# MODULO_CONTROL.net
KiCad netlist of a schematic drawn in Altium Designer
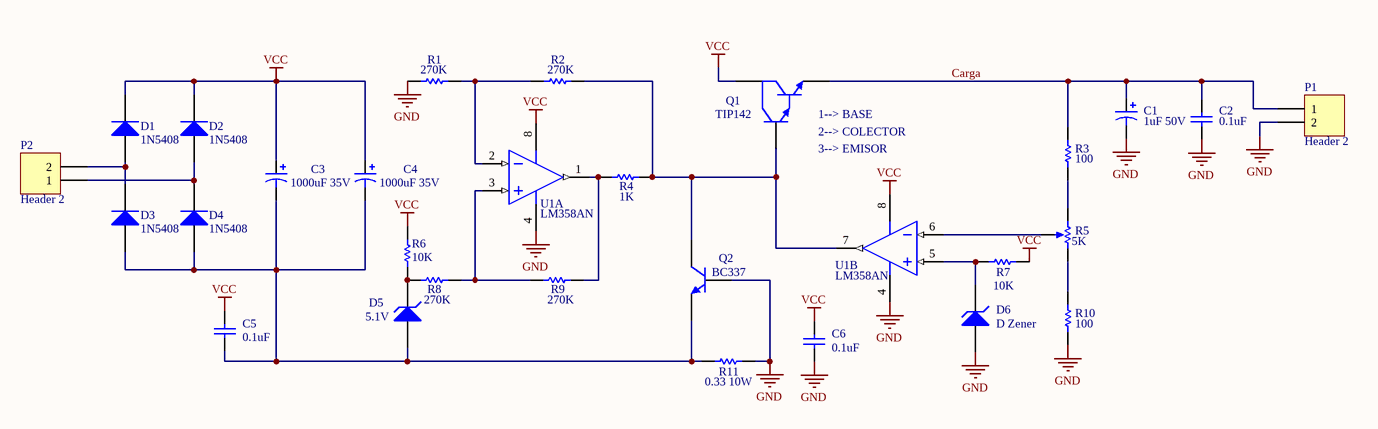
[diagram p0: MODULO CONTROL.SchDoc]

(export (version "E")
  (design (tool "Eeschema 10.0.6"))
  (components
    (comp (ref "C1")
      (value "1uF 50V")
      (footprint "CAPPR2-5x6.8")
      (description "Polarized Capacitor (Radial)")
      (fields (field (name "Comment") "Cap Pol1") (field (name "PUBLISHER") "Altium Limited"))
      (libsource (lib "Miscellaneous Devices") (part "Cap Pol1"))
    )
    (comp (ref "C2")
      (value "0.1uF")
      (footprint "Miscellaneous Devices:RAD-0.2")
      (description "Capacitor")
      (fields (field (name "Comment") "Cap") (field (name "PUBLISHER") "Altium Limited"))
      (libsource (lib "Miscellaneous Devices") (part "Cap"))
    )
    (comp (ref "C3")
      (value "1000uF 35V")
      (footprint "RB5-10.5")
      (description "Polarized Capacitor (Radial)")
      (fields (field (name "Comment") "Cap Pol1") (field (name "PUBLISHER") "Altium Limited"))
      (libsource (lib "Miscellaneous Devices") (part "Cap Pol1"))
    )
    (comp (ref "C4")
      (value "1000uF 35V")
      (footprint "RB5-10.5")
      (description "Polarized Capacitor (Radial)")
      (fields (field (name "Comment") "Cap Pol1") (field (name "PUBLISHER") "Altium Limited"))
      (libsource (lib "Miscellaneous Devices") (part "Cap Pol1"))
    )
    (comp (ref "C5")
      (value "0.1uF")
      (footprint "Miscellaneous Devices:RAD-0.2")
      (description "Capacitor")
      (fields (field (name "Comment") "Cap") (field (name "PUBLISHER") "Altium Limited"))
      (libsource (lib "Miscellaneous Devices") (part "Cap"))
    )
    (comp (ref "C6")
      (value "0.1uF")
      (footprint "RAD-0.2")
      (description "Capacitor")
      (fields (field (name "Comment") "Cap") (field (name "PUBLISHER") "Altium Limited"))
      (libsource (lib "Miscellaneous Devices") (part "Cap"))
    )
    (comp (ref "D1")
      (value "1N5408")
      (footprint "DIO18.84-9.6x5.6")
      (description "3 Amp Medium Power Silicon Rectifier Diode")
      (fields (field (name "PUBLISHER") "Altium Limited"))
      (libsource (lib "Miscellaneous Devices") (part "Diode 1N5408"))
    )
    (comp (ref "D2")
      (value "1N5408")
      (footprint "DIO18.84-9.6x5.6")
      (description "3 Amp Medium Power Silicon Rectifier Diode")
      (fields (field (name "PUBLISHER") "Altium Limited"))
      (libsource (lib "Miscellaneous Devices") (part "Diode 1N5408"))
    )
    (comp (ref "D3")
      (value "1N5408")
      (footprint "DIO18.84-9.6x5.6")
      (description "3 Amp Medium Power Silicon Rectifier Diode")
      (fields (field (name "PUBLISHER") "Altium Limited"))
      (libsource (lib "Miscellaneous Devices") (part "Diode 1N5408"))
    )
    (comp (ref "D4")
      (value "1N5408")
      (footprint "DIO18.84-9.6x5.6")
      (description "3 Amp Medium Power Silicon Rectifier Diode")
      (fields (field (name "PUBLISHER") "Altium Limited"))
      (libsource (lib "Miscellaneous Devices") (part "Diode 1N5408"))
    )
    (comp (ref "D5")
      (value "5.1V")
      (footprint "DIODE-0.4")
      (description "Zener Diode")
      (fields (field (name "PUBLISHER") "Altium Limited"))
      (libsource (lib "Miscellaneous Devices") (part "D Zener"))
    )
    (comp (ref "D6")
      (value "D Zener")
      (footprint "DIODE-0.4")
      (description "Zener Diode")
      (fields (field (name "PUBLISHER") "Altium Limited"))
      (libsource (lib "Miscellaneous Devices") (part "D Zener"))
    )
    (comp (ref "P1")
      (value "Header 2")
      (footprint "RAD-0.2")
      (description "Header, 2-Pin")
      (fields (field (name "PUBLISHER") "Altium Limited"))
      (libsource (lib "") (part "Header 2_1"))
    )
    (comp (ref "P2")
      (value "Header 2")
      (footprint "RAD-0.2")
      (description "Header, 2-Pin")
      (fields (field (name "PUBLISHER") "Altium Limited"))
      (libsource (lib "Miscellaneous Connectors") (part "Header 2"))
    )
    (comp (ref "Q1")
      (value "TIP142")
      (footprint "340K-01")
      (description "NPN Darlington Bipolar Transistor")
      (fields (field (name "PUBLISHER") "Altium Limited"))
      (libsource (lib "Miscellaneous Devices") (part "NPN1"))
    )
    (comp (ref "Q2")
      (value "BC337")
      (footprint "BCY-W3")
      (description "NPN Bipolar Transistor")
      (fields (field (name "PUBLISHER") "Altium Limited"))
      (libsource (lib "Miscellaneous Devices") (part "NPN"))
    )
    (comp (ref "R1")
      (value "270K")
      (footprint "AXIAL-0.4")
      (description "Resistor")
      (fields (field (name "Comment") "Res1") (field (name "PUBLISHER") "Altium Limited"))
      (libsource (lib "Miscellaneous Devices") (part "Res1"))
    )
    (comp (ref "R2")
      (value "270K")
      (footprint "AXIAL-0.4")
      (description "Resistor")
      (fields (field (name "Comment") "Res1") (field (name "PUBLISHER") "Altium Limited"))
      (libsource (lib "Miscellaneous Devices") (part "Res1"))
    )
    (comp (ref "R3")
      (value "100")
      (footprint "AXIAL-0.4")
      (description "Resistor")
      (fields (field (name "Comment") "Res1") (field (name "PUBLISHER") "Altium Limited"))
      (libsource (lib "Miscellaneous Devices") (part "Res1"))
    )
    (comp (ref "R4")
      (value "1K")
      (footprint "AXIAL-0.4")
      (description "Resistor")
      (fields (field (name "Comment") "Res1") (field (name "PUBLISHER") "Altium Limited"))
      (libsource (lib "Miscellaneous Devices") (part "Res1"))
    )
    (comp (ref "R5")
      (value "5K")
      (footprint "VR5")
      (description "Potentiometer")
      (fields (field (name "Comment") "RPot") (field (name "PUBLISHER") "Altium Limited"))
      (libsource (lib "Miscellaneous Devices") (part "RPot"))
    )
    (comp (ref "R6")
      (value "10K")
      (footprint "AXIAL-0.4")
      (description "Resistor")
      (fields (field (name "Comment") "Res1") (field (name "PUBLISHER") "Altium Limited"))
      (libsource (lib "Miscellaneous Devices") (part "Res1"))
    )
    (comp (ref "R7")
      (value "10K")
      (footprint "AXIAL-0.4")
      (description "Resistor")
      (fields (field (name "Comment") "Res1") (field (name "PUBLISHER") "Altium Limited"))
      (libsource (lib "Miscellaneous Devices") (part "Res1"))
    )
    (comp (ref "R8")
      (value "270K")
      (footprint "AXIAL-0.4")
      (description "Resistor")
      (fields (field (name "Comment") "Res1") (field (name "PUBLISHER") "Altium Limited"))
      (libsource (lib "Miscellaneous Devices") (part "Res1"))
    )
    (comp (ref "R9")
      (value "270K")
      (footprint "AXIAL-0.4")
      (description "Resistor")
      (fields (field (name "Comment") "Res1") (field (name "PUBLISHER") "Altium Limited"))
      (libsource (lib "Miscellaneous Devices") (part "Res1"))
    )
    (comp (ref "R10")
      (value "100")
      (footprint "AXIAL-0.4")
      (description "Resistor")
      (fields (field (name "Comment") "Res1") (field (name "PUBLISHER") "Altium Limited"))
      (libsource (lib "Miscellaneous Devices") (part "Res1"))
    )
    (comp (ref "R11")
      (value "0.33 10W")
      (footprint "AXIAL-1.0")
      (description "Resistor")
      (fields (field (name "Comment") "Res1") (field (name "PUBLISHER") "Altium Limited"))
      (libsource (lib "Miscellaneous Devices") (part "Res1"))
    )
    (comp (ref "U1")
      (value "LM358AN")
      (footprint "N08E")
      (description "Low Power Dual Operational Amplifier")
      (fields
        (field (name "MANUFACTURER") "National Semiconductor")
        (field (name "DIGIKEYPARTNUMBER") "LM358ANNS-ND")
        (field (name "PUBLISHER") "Altium Limited")
      )
      (libsource (lib "NSC Amplifier") (part "LM358AN"))
    )
  )
  (nets
    (net (code "1") (name "/Carga") (class "Default")
      (node (ref "C1") (pin "1") (pinfunction "1_1") (pintype "passive"))
      (node (ref "C2") (pin "2") (pinfunction "2_2") (pintype "passive"))
      (node (ref "P1") (pin "1") (pinfunction "1_1") (pintype "passive"))
      (node (ref "Q1") (pin "3") (pinfunction "E_3") (pintype "passive"))
      (node (ref "R3") (pin "2") (pinfunction "2_2") (pintype "passive"))
    )
    (net (code "2") (name "GND") (class "Default")
      (node (ref "C1") (pin "2") (pinfunction "2_2") (pintype "passive"))
      (node (ref "C2") (pin "1") (pinfunction "1_1") (pintype "passive"))
      (node (ref "C6") (pin "1") (pinfunction "1_1") (pintype "passive"))
      (node (ref "D6") (pin "1") (pinfunction "A_1") (pintype "passive"))
      (node (ref "P1") (pin "2") (pinfunction "2_2") (pintype "passive"))
      (node (ref "Q2") (pin "2") (pinfunction "B_2") (pintype "passive"))
      (node (ref "R1") (pin "1") (pinfunction "1_1") (pintype "passive"))
      (node (ref "R10") (pin "1") (pinfunction "1_1") (pintype "passive"))
      (node (ref "R11") (pin "2") (pinfunction "2_2") (pintype "passive"))
      (node (ref "U1") (pin "4") (pinfunction "GND_4") (pintype "power_in"))
    )
    (net (code "3") (name "Net-(D1-A)") (class "Default")
      (node (ref "D1") (pin "1") (pinfunction "A_1") (pintype "passive"))
      (node (ref "D3") (pin "2") (pinfunction "K_2") (pintype "passive"))
      (node (ref "P2") (pin "2") (pinfunction "2_2") (pintype "passive"))
    )
    (net (code "4") (name "Net-(D2-A)") (class "Default")
      (node (ref "D2") (pin "1") (pinfunction "A_1") (pintype "passive"))
      (node (ref "D4") (pin "2") (pinfunction "K_2") (pintype "passive"))
      (node (ref "P2") (pin "1") (pinfunction "1_1") (pintype "passive"))
    )
    (net (code "5") (name "Net-(D3-A)") (class "Default")
      (node (ref "C3") (pin "2") (pinfunction "2_2") (pintype "passive"))
      (node (ref "C4") (pin "2") (pinfunction "2_2") (pintype "passive"))
      (node (ref "C5") (pin "1") (pinfunction "1_1") (pintype "passive"))
      (node (ref "D3") (pin "1") (pinfunction "A_1") (pintype "passive"))
      (node (ref "D4") (pin "1") (pinfunction "A_1") (pintype "passive"))
      (node (ref "D5") (pin "1") (pinfunction "A_1") (pintype "passive"))
      (node (ref "Q2") (pin "3") (pinfunction "E_3") (pintype "passive"))
      (node (ref "R11") (pin "1") (pinfunction "1_1") (pintype "passive"))
    )
    (net (code "6") (name "Net-(D5-K)") (class "Default")
      (node (ref "D5") (pin "2") (pinfunction "K_2") (pintype "passive"))
      (node (ref "R6") (pin "1") (pinfunction "1_1") (pintype "passive"))
      (node (ref "R8") (pin "1") (pinfunction "1_1") (pintype "passive"))
    )
    (net (code "7") (name "Net-(D6-K)") (class "Default")
      (node (ref "D6") (pin "2") (pinfunction "K_2") (pintype "passive"))
      (node (ref "R7") (pin "1") (pinfunction "1_1") (pintype "passive"))
      (node (ref "U1") (pin "5") (pinfunction "INB+_5") (pintype "input"))
    )
    (net (code "8") (name "Net-(Q1-B)") (class "Default")
      (node (ref "Q1") (pin "2") (pinfunction "B_2") (pintype "passive"))
      (node (ref "Q2") (pin "1") (pinfunction "C_1") (pintype "passive"))
      (node (ref "R2") (pin "2") (pinfunction "2_2") (pintype "passive"))
      (node (ref "R4") (pin "2") (pinfunction "2_2") (pintype "passive"))
      (node (ref "U1") (pin "7") (pinfunction "OUTB_7") (pintype "output"))
    )
    (net (code "9") (name "Net-(R5-BOT)") (class "Default")
      (node (ref "R10") (pin "2") (pinfunction "2_2") (pintype "passive"))
      (node (ref "R5") (pin "2") (pinfunction "BOT_2") (pintype "passive"))
    )
    (net (code "10") (name "Net-(R5-TAP)") (class "Default")
      (node (ref "R5") (pin "3") (pinfunction "TAP_3") (pintype "passive"))
      (node (ref "U1") (pin "6") (pinfunction "INB-_6") (pintype "input"))
    )
    (net (code "11") (name "Net-(R5-TOP)") (class "Default")
      (node (ref "R3") (pin "1") (pinfunction "1_1") (pintype "passive"))
      (node (ref "R5") (pin "1") (pinfunction "TOP_1") (pintype "passive"))
    )
    (net (code "12") (name "Net-(U1A-INA+)") (class "Default")
      (node (ref "R8") (pin "2") (pinfunction "2_2") (pintype "passive"))
      (node (ref "R9") (pin "1") (pinfunction "1_1") (pintype "passive"))
      (node (ref "U1") (pin "3") (pinfunction "INA+_3") (pintype "input"))
    )
    (net (code "13") (name "Net-(U1A-INA-)") (class "Default")
      (node (ref "R1") (pin "2") (pinfunction "2_2") (pintype "passive"))
      (node (ref "R2") (pin "1") (pinfunction "1_1") (pintype "passive"))
      (node (ref "U1") (pin "2") (pinfunction "INA-_2") (pintype "input"))
    )
    (net (code "14") (name "Net-(U1A-OUTA)") (class "Default")
      (node (ref "R4") (pin "1") (pinfunction "1_1") (pintype "passive"))
      (node (ref "R9") (pin "2") (pinfunction "2_2") (pintype "passive"))
      (node (ref "U1") (pin "1") (pinfunction "OUTA_1") (pintype "output"))
    )
    (net (code "15") (name "VCC") (class "Default")
      (node (ref "C3") (pin "1") (pinfunction "1_1") (pintype "passive"))
      (node (ref "C4") (pin "1") (pinfunction "1_1") (pintype "passive"))
      (node (ref "C5") (pin "2") (pinfunction "2_2") (pintype "passive"))
      (node (ref "C6") (pin "2") (pinfunction "2_2") (pintype "passive"))
      (node (ref "D1") (pin "2") (pinfunction "K_2") (pintype "passive"))
      (node (ref "D2") (pin "2") (pinfunction "K_2") (pintype "passive"))
      (node (ref "Q1") (pin "1") (pinfunction "C_1") (pintype "passive"))
      (node (ref "R6") (pin "2") (pinfunction "2_2") (pintype "passive"))
      (node (ref "R7") (pin "2") (pinfunction "2_2") (pintype "passive"))
      (node (ref "U1") (pin "8") (pinfunction "V+_8") (pintype "power_in"))
    )
  )
)
